# w076x.net
KiCad netlist of a schematic drawn in EAGLE
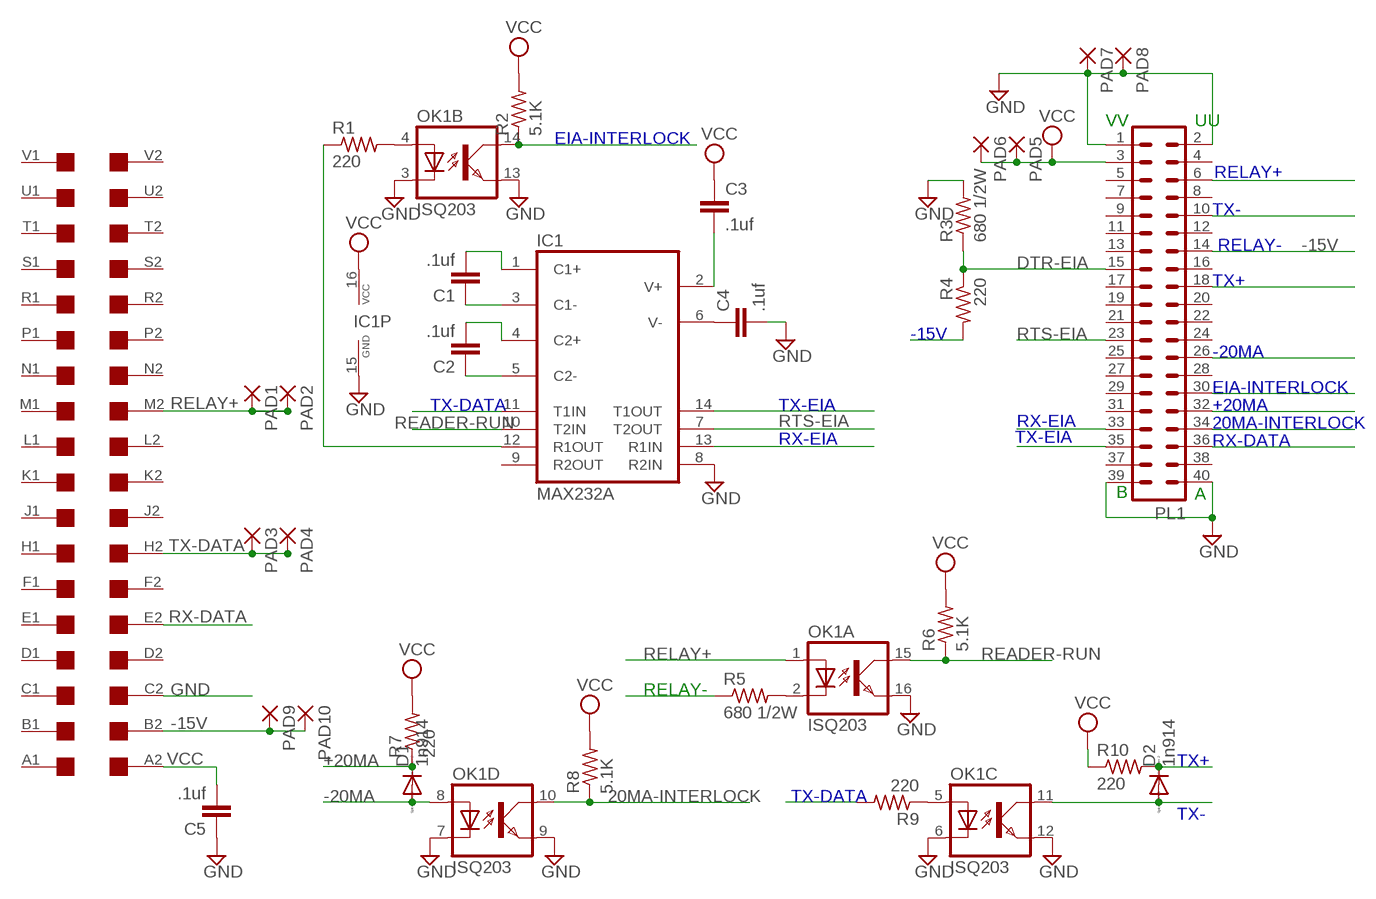
[diagram p0: schematic, sheet 1]

(export (version "E")
  (design (tool "Eeschema 10.0.6"))
  (components
    (comp (ref "C1")
      (value ".1uf")
      (footprint "eagle-import:C050-025X075")
      (libsource (lib "eagle-import") (part "C-EU050-025X075"))
    )
    (comp (ref "C2")
      (value ".1uf")
      (footprint "eagle-import:C050-025X075")
      (libsource (lib "eagle-import") (part "C-EU050-025X075"))
    )
    (comp (ref "C3")
      (value ".1uf")
      (footprint "eagle-import:C050-025X075")
      (libsource (lib "eagle-import") (part "C-EU050-025X075"))
    )
    (comp (ref "C4")
      (value ".1uf")
      (footprint "eagle-import:C050-025X075")
      (libsource (lib "eagle-import") (part "C-EU050-025X075"))
    )
    (comp (ref "C5")
      (value ".1uf")
      (footprint "eagle-import:C050-025X075")
      (libsource (lib "eagle-import") (part "C-EU050-025X075"))
    )
    (comp (ref "D1")
      (value "1n914")
      (footprint "eagle-import:DO41-10")
      (libsource (lib "eagle-import") (part "1N4004"))
    )
    (comp (ref "D2")
      (value "1n914")
      (footprint "eagle-import:DO41-10")
      (libsource (lib "eagle-import") (part "1N4004"))
    )
    (comp (ref "IC1")
      (value "MAX232A")
      (footprint "eagle-import:DIL16")
      (fields (field (name "MF") "MAXIM") (field (name "MPN") "MAX232ACPE+"))
      (libsource (lib "eagle-import") (part "MAX232"))
    )
    (comp (ref "OK1")
      (value "ISQ203")
      (footprint "eagle-import:DIL16")
      (fields (field (name "MF") "VISHAY/TELEFUNKEN") (field (name "MPN") "ILQ1"))
      (libsource (lib "eagle-import") (part "ILQ1"))
    )
    (comp (ref "PAD1")
      (value "1,6/0,8")
      (footprint "eagle-import:1,6_0,8")
      (libsource (lib "eagle-import") (part "1,6/0,8"))
    )
    (comp (ref "PAD2")
      (value "1,6/0,8")
      (footprint "eagle-import:1,6_0,8")
      (libsource (lib "eagle-import") (part "1,6/0,8"))
    )
    (comp (ref "PAD3")
      (value "1,6/0,8")
      (footprint "eagle-import:1,6_0,8")
      (libsource (lib "eagle-import") (part "1,6/0,8"))
    )
    (comp (ref "PAD4")
      (value "1,6/0,8")
      (footprint "eagle-import:1,6_0,8")
      (libsource (lib "eagle-import") (part "1,6/0,8"))
    )
    (comp (ref "PAD5")
      (value "1,6/0,8")
      (footprint "eagle-import:1,6_0,8")
      (libsource (lib "eagle-import") (part "1,6/0,8"))
    )
    (comp (ref "PAD6")
      (value "1,6/0,8")
      (footprint "eagle-import:1,6_0,8")
      (libsource (lib "eagle-import") (part "1,6/0,8"))
    )
    (comp (ref "PAD7")
      (value "1,6/0,8")
      (footprint "eagle-import:1,6_0,8")
      (libsource (lib "eagle-import") (part "1,6/0,8"))
    )
    (comp (ref "PAD8")
      (value "1,6/0,8")
      (footprint "eagle-import:1,6_0,8")
      (libsource (lib "eagle-import") (part "1,6/0,8"))
    )
    (comp (ref "PAD9")
      (value "1,6/0,8")
      (footprint "eagle-import:1,6_0,8")
      (libsource (lib "eagle-import") (part "1,6/0,8"))
    )
    (comp (ref "PAD10")
      (value "1,6/0,8")
      (footprint "eagle-import:1,6_0,8")
      (libsource (lib "eagle-import") (part "1,6/0,8"))
    )
    (comp (ref "PL1")
      (value "40H")
      (footprint "eagle-import:40H")
      (libsource (lib "eagle-import") (part "40H"))
    )
    (comp (ref "R1")
      (value "220")
      (footprint "eagle-import:0207_10")
      (libsource (lib "eagle-import") (part "R-US_0207/10"))
    )
    (comp (ref "R2")
      (value "5.1K")
      (footprint "eagle-import:0207_10")
      (libsource (lib "eagle-import") (part "R-US_0207/10"))
    )
    (comp (ref "R3")
      (value "680 1/2W")
      (footprint "eagle-import:0207_12")
      (libsource (lib "eagle-import") (part "R-US_0207/12"))
    )
    (comp (ref "R4")
      (value "220")
      (footprint "eagle-import:0207_10")
      (libsource (lib "eagle-import") (part "R-US_0207/10"))
    )
    (comp (ref "R5")
      (value "680 1/2W")
      (footprint "eagle-import:0207_12")
      (libsource (lib "eagle-import") (part "R-US_0207/12"))
    )
    (comp (ref "R6")
      (value "5.1K")
      (footprint "eagle-import:0207_10")
      (libsource (lib "eagle-import") (part "R-US_0207/10"))
    )
    (comp (ref "R7")
      (value "220")
      (footprint "eagle-import:0207_10")
      (libsource (lib "eagle-import") (part "R-US_0207/10"))
    )
    (comp (ref "R8")
      (value "5.1K")
      (footprint "eagle-import:0207_10")
      (libsource (lib "eagle-import") (part "R-US_0207/10"))
    )
    (comp (ref "R9")
      (value "220")
      (footprint "eagle-import:0207_10")
      (libsource (lib "eagle-import") (part "R-US_0207/10"))
    )
    (comp (ref "R10")
      (value "220")
      (footprint "eagle-import:0207_10")
      (libsource (lib "eagle-import") (part "R-US_0207/10"))
    )
    (comp (ref "U$1")
      (value "DEC-FLIPCHIP")
      (footprint "eagle-import:DEC-FLIPCHIP")
      (libsource (lib "eagle-import") (part "DEC-FLIPCHIP"))
    )
  )
  (nets
    (net (code "1") (name "/+20MA") (class "Default")
      (node (ref "D1") (pin "C") (pinfunction "C_C") (pintype "passive"))
      (node (ref "PL1") (pin "32") (pinfunction "32_32") (pintype "passive"))
      (node (ref "R7") (pin "1") (pinfunction "1_1") (pintype "passive"))
    )
    (net (code "2") (name "/-15V") (class "Default")
      (node (ref "PAD10") (pin "1") (pinfunction "P_1") (pintype "passive"))
      (node (ref "PAD9") (pin "1") (pinfunction "P_1") (pintype "passive"))
      (node (ref "PL1") (pin "14") (pinfunction "14_14") (pintype "passive"))
      (node (ref "R4") (pin "2") (pinfunction "2_2") (pintype "passive"))
      (node (ref "R5") (pin "1") (pinfunction "1_1") (pintype "passive"))
      (node (ref "U$1") (pin "B2") (pinfunction "B2_B2") (pintype "passive"))
    )
    (net (code "3") (name "/-20MA") (class "Default")
      (node (ref "D1") (pin "A") (pinfunction "A_A") (pintype "passive"))
      (node (ref "OK1") (pin "8") (pinfunction "A_8") (pintype "passive"))
      (node (ref "PL1") (pin "26") (pinfunction "26_26") (pintype "passive"))
    )
    (net (code "4") (name "/20MA-INTERLOCK") (class "Default")
      (node (ref "OK1") (pin "10") (pinfunction "COL_10") (pintype "passive"))
      (node (ref "PL1") (pin "34") (pinfunction "34_34") (pintype "passive"))
      (node (ref "R8") (pin "1") (pinfunction "1_1") (pintype "passive"))
    )
    (net (code "5") (name "/DTR-EIA") (class "Default")
      (node (ref "PL1") (pin "15") (pinfunction "15_15") (pintype "passive"))
      (node (ref "R3") (pin "1") (pinfunction "1_1") (pintype "passive"))
      (node (ref "R4") (pin "1") (pinfunction "1_1") (pintype "passive"))
    )
    (net (code "6") (name "/EIA-INTERLOCK") (class "Default")
      (node (ref "OK1") (pin "14") (pinfunction "COL_14") (pintype "passive"))
      (node (ref "PL1") (pin "30") (pinfunction "30_30") (pintype "passive"))
      (node (ref "R2") (pin "1") (pinfunction "1_1") (pintype "passive"))
    )
    (net (code "7") (name "/READER-RUN") (class "Default")
      (node (ref "IC1") (pin "10") (pinfunction "T2IN_10") (pintype "input"))
      (node (ref "OK1") (pin "15") (pinfunction "COL_15") (pintype "passive"))
      (node (ref "R6") (pin "1") (pinfunction "1_1") (pintype "passive"))
    )
    (net (code "8") (name "/RELAY+") (class "Default")
      (node (ref "OK1") (pin "1") (pinfunction "A_1") (pintype "passive"))
      (node (ref "PAD1") (pin "1") (pinfunction "P_1") (pintype "passive"))
      (node (ref "PAD2") (pin "1") (pinfunction "P_1") (pintype "passive"))
      (node (ref "PL1") (pin "6") (pinfunction "6_6") (pintype "passive"))
      (node (ref "U$1") (pin "M2") (pinfunction "M2_M2") (pintype "passive"))
    )
    (net (code "9") (name "/RTS-EIA") (class "Default")
      (node (ref "IC1") (pin "7") (pinfunction "T2OUT_7") (pintype "output"))
      (node (ref "PL1") (pin "23") (pinfunction "23_23") (pintype "passive"))
    )
    (net (code "10") (name "/RX-DATA") (class "Default")
      (node (ref "PL1") (pin "36") (pinfunction "36_36") (pintype "passive"))
      (node (ref "U$1") (pin "E2") (pinfunction "E2_E2") (pintype "passive"))
    )
    (net (code "11") (name "/RX-EIA") (class "Default")
      (node (ref "IC1") (pin "13") (pinfunction "R1IN_13") (pintype "input"))
      (node (ref "PL1") (pin "33") (pinfunction "33_33") (pintype "passive"))
    )
    (net (code "12") (name "/TX+") (class "Default")
      (node (ref "D2") (pin "C") (pinfunction "C_C") (pintype "passive"))
      (node (ref "PL1") (pin "18") (pinfunction "18_18") (pintype "passive"))
      (node (ref "R10") (pin "2") (pinfunction "2_2") (pintype "passive"))
    )
    (net (code "13") (name "/TX-") (class "Default")
      (node (ref "D2") (pin "A") (pinfunction "A_A") (pintype "passive"))
      (node (ref "OK1") (pin "11") (pinfunction "COL_11") (pintype "passive"))
      (node (ref "PL1") (pin "10") (pinfunction "10_10") (pintype "passive"))
    )
    (net (code "14") (name "/TX-DATA") (class "Default")
      (node (ref "IC1") (pin "11") (pinfunction "T1IN_11") (pintype "input"))
      (node (ref "PAD3") (pin "1") (pinfunction "P_1") (pintype "passive"))
      (node (ref "PAD4") (pin "1") (pinfunction "P_1") (pintype "passive"))
      (node (ref "R9") (pin "2") (pinfunction "2_2") (pintype "passive"))
      (node (ref "U$1") (pin "H2") (pinfunction "H2_H2") (pintype "passive"))
    )
    (net (code "15") (name "/TX-EIA") (class "Default")
      (node (ref "IC1") (pin "14") (pinfunction "T1OUT_14") (pintype "output"))
      (node (ref "PL1") (pin "35") (pinfunction "35_35") (pintype "passive"))
    )
    (net (code "16") (name "GND") (class "Default")
      (node (ref "C4") (pin "2") (pinfunction "2_2") (pintype "passive"))
      (node (ref "C5") (pin "1") (pinfunction "1_1") (pintype "passive"))
      (node (ref "IC1") (pin "15") (pinfunction "GND_15") (pintype "power_in"))
      (node (ref "IC1") (pin "8") (pinfunction "R2IN_8") (pintype "input"))
      (node (ref "OK1") (pin "12") (pinfunction "EMIT_12") (pintype "passive"))
      (node (ref "OK1") (pin "13") (pinfunction "EMIT_13") (pintype "passive"))
      (node (ref "OK1") (pin "16") (pinfunction "EMIT_16") (pintype "passive"))
      (node (ref "OK1") (pin "3") (pinfunction "C_3") (pintype "passive"))
      (node (ref "OK1") (pin "6") (pinfunction "C_6") (pintype "passive"))
      (node (ref "OK1") (pin "7") (pinfunction "C_7") (pintype "passive"))
      (node (ref "OK1") (pin "9") (pinfunction "EMIT_9") (pintype "passive"))
      (node (ref "PAD7") (pin "1") (pinfunction "P_1") (pintype "passive"))
      (node (ref "PAD8") (pin "1") (pinfunction "P_1") (pintype "passive"))
      (node (ref "PL1") (pin "1") (pinfunction "1_1") (pintype "passive"))
      (node (ref "PL1") (pin "2") (pinfunction "2_2") (pintype "passive"))
      (node (ref "PL1") (pin "39") (pinfunction "39_39") (pintype "passive"))
      (node (ref "PL1") (pin "40") (pinfunction "40_40") (pintype "passive"))
      (node (ref "R3") (pin "2") (pinfunction "2_2") (pintype "passive"))
      (node (ref "U$1") (pin "C2") (pinfunction "C2_C2") (pintype "passive"))
    )
    (net (code "17") (name "Net-(IC1A-C1+)") (class "Default")
      (node (ref "C1") (pin "2") (pinfunction "2_2") (pintype "passive"))
      (node (ref "IC1") (pin "1") (pinfunction "C1+_1") (pintype "bidirectional"))
    )
    (net (code "18") (name "Net-(IC1A-C1-)") (class "Default")
      (node (ref "C1") (pin "1") (pinfunction "1_1") (pintype "passive"))
      (node (ref "IC1") (pin "3") (pinfunction "C1-_3") (pintype "bidirectional"))
    )
    (net (code "19") (name "Net-(IC1A-C2+)") (class "Default")
      (node (ref "C2") (pin "2") (pinfunction "2_2") (pintype "passive"))
      (node (ref "IC1") (pin "4") (pinfunction "C2+_4") (pintype "bidirectional"))
    )
    (net (code "20") (name "Net-(IC1A-C2-)") (class "Default")
      (node (ref "C2") (pin "1") (pinfunction "1_1") (pintype "passive"))
      (node (ref "IC1") (pin "5") (pinfunction "C2-_5") (pintype "bidirectional"))
    )
    (net (code "21") (name "Net-(IC1A-R1OUT)") (class "Default")
      (node (ref "IC1") (pin "12") (pinfunction "R1OUT_12") (pintype "output"))
      (node (ref "R1") (pin "1") (pinfunction "1_1") (pintype "passive"))
    )
    (net (code "22") (name "Net-(IC1A-V+)") (class "Default")
      (node (ref "C3") (pin "2") (pinfunction "2_2") (pintype "passive"))
      (node (ref "IC1") (pin "2") (pinfunction "V+_2") (pintype "bidirectional"))
    )
    (net (code "23") (name "Net-(IC1A-V-)") (class "Default")
      (node (ref "C4") (pin "1") (pinfunction "1_1") (pintype "passive"))
      (node (ref "IC1") (pin "6") (pinfunction "V-_6") (pintype "bidirectional"))
    )
    (net (code "24") (name "Net-(OK1A-C)") (class "Default")
      (node (ref "OK1") (pin "2") (pinfunction "C_2") (pintype "passive"))
      (node (ref "R5") (pin "2") (pinfunction "2_2") (pintype "passive"))
    )
    (net (code "25") (name "Net-(OK1B-A)") (class "Default")
      (node (ref "OK1") (pin "4") (pinfunction "A_4") (pintype "passive"))
      (node (ref "R1") (pin "2") (pinfunction "2_2") (pintype "passive"))
    )
    (net (code "26") (name "Net-(OK1C-A)") (class "Default")
      (node (ref "OK1") (pin "5") (pinfunction "A_5") (pintype "passive"))
      (node (ref "R9") (pin "1") (pinfunction "1_1") (pintype "passive"))
    )
    (net (code "27") (name "VCC") (class "Default")
      (node (ref "C3") (pin "1") (pinfunction "1_1") (pintype "passive"))
      (node (ref "C5") (pin "2") (pinfunction "2_2") (pintype "passive"))
      (node (ref "IC1") (pin "16") (pinfunction "VCC_16") (pintype "power_in"))
      (node (ref "PAD5") (pin "1") (pinfunction "P_1") (pintype "passive"))
      (node (ref "PAD6") (pin "1") (pinfunction "P_1") (pintype "passive"))
      (node (ref "PL1") (pin "3") (pinfunction "3_3") (pintype "passive"))
      (node (ref "R10") (pin "1") (pinfunction "1_1") (pintype "passive"))
      (node (ref "R2") (pin "2") (pinfunction "2_2") (pintype "passive"))
      (node (ref "R6") (pin "2") (pinfunction "2_2") (pintype "passive"))
      (node (ref "R7") (pin "2") (pinfunction "2_2") (pintype "passive"))
      (node (ref "R8") (pin "2") (pinfunction "2_2") (pintype "passive"))
      (node (ref "U$1") (pin "A2") (pinfunction "A2_A2") (pintype "passive"))
    )
    (net (code "28") (name "unconnected-(IC1A-R2OUT-Pad9)") (class "Default")
      (node (ref "IC1") (pin "9") (pinfunction "R2OUT_9") (pintype "output"))
    )
    (net (code "29") (name "unconnected-(PL1-Pad4)") (class "Default")
      (node (ref "PL1") (pin "4") (pinfunction "4_4") (pintype "passive"))
    )
    (net (code "30") (name "unconnected-(PL1-Pad5)") (class "Default")
      (node (ref "PL1") (pin "5") (pinfunction "5_5") (pintype "passive"))
    )
    (net (code "31") (name "unconnected-(PL1-Pad7)") (class "Default")
      (node (ref "PL1") (pin "7") (pinfunction "7_7") (pintype "passive"))
    )
    (net (code "32") (name "unconnected-(PL1-Pad8)") (class "Default")
      (node (ref "PL1") (pin "8") (pinfunction "8_8") (pintype "passive"))
    )
    (net (code "33") (name "unconnected-(PL1-Pad9)") (class "Default")
      (node (ref "PL1") (pin "9") (pinfunction "9_9") (pintype "passive"))
    )
    (net (code "34") (name "unconnected-(PL1-Pad11)") (class "Default")
      (node (ref "PL1") (pin "11") (pinfunction "11_11") (pintype "passive"))
    )
    (net (code "35") (name "unconnected-(PL1-Pad12)") (class "Default")
      (node (ref "PL1") (pin "12") (pinfunction "12_12") (pintype "passive"))
    )
    (net (code "36") (name "unconnected-(PL1-Pad13)") (class "Default")
      (node (ref "PL1") (pin "13") (pinfunction "13_13") (pintype "passive"))
    )
    (net (code "37") (name "unconnected-(PL1-Pad16)") (class "Default")
      (node (ref "PL1") (pin "16") (pinfunction "16_16") (pintype "passive"))
    )
    (net (code "38") (name "unconnected-(PL1-Pad17)") (class "Default")
      (node (ref "PL1") (pin "17") (pinfunction "17_17") (pintype "passive"))
    )
    (net (code "39") (name "unconnected-(PL1-Pad19)") (class "Default")
      (node (ref "PL1") (pin "19") (pinfunction "19_19") (pintype "passive"))
    )
    (net (code "40") (name "unconnected-(PL1-Pad20)") (class "Default")
      (node (ref "PL1") (pin "20") (pinfunction "20_20") (pintype "passive"))
    )
    (net (code "41") (name "unconnected-(PL1-Pad21)") (class "Default")
      (node (ref "PL1") (pin "21") (pinfunction "21_21") (pintype "passive"))
    )
    (net (code "42") (name "unconnected-(PL1-Pad22)") (class "Default")
      (node (ref "PL1") (pin "22") (pinfunction "22_22") (pintype "passive"))
    )
    (net (code "43") (name "unconnected-(PL1-Pad24)") (class "Default")
      (node (ref "PL1") (pin "24") (pinfunction "24_24") (pintype "passive"))
    )
    (net (code "44") (name "unconnected-(PL1-Pad25)") (class "Default")
      (node (ref "PL1") (pin "25") (pinfunction "25_25") (pintype "passive"))
    )
    (net (code "45") (name "unconnected-(PL1-Pad27)") (class "Default")
      (node (ref "PL1") (pin "27") (pinfunction "27_27") (pintype "passive"))
    )
    (net (code "46") (name "unconnected-(PL1-Pad28)") (class "Default")
      (node (ref "PL1") (pin "28") (pinfunction "28_28") (pintype "passive"))
    )
    (net (code "47") (name "unconnected-(PL1-Pad29)") (class "Default")
      (node (ref "PL1") (pin "29") (pinfunction "29_29") (pintype "passive"))
    )
    (net (code "48") (name "unconnected-(PL1-Pad31)") (class "Default")
      (node (ref "PL1") (pin "31") (pinfunction "31_31") (pintype "passive"))
    )
    (net (code "49") (name "unconnected-(PL1-Pad37)") (class "Default")
      (node (ref "PL1") (pin "37") (pinfunction "37_37") (pintype "passive"))
    )
    (net (code "50") (name "unconnected-(PL1-Pad38)") (class "Default")
      (node (ref "PL1") (pin "38") (pinfunction "38_38") (pintype "passive"))
    )
    (net (code "51") (name "unconnected-(U$1-PadA1)") (class "Default")
      (node (ref "U$1") (pin "A1") (pinfunction "A1_A1") (pintype "passive"))
    )
    (net (code "52") (name "unconnected-(U$1-PadB1)") (class "Default")
      (node (ref "U$1") (pin "B1") (pinfunction "B1_B1") (pintype "passive"))
    )
    (net (code "53") (name "unconnected-(U$1-PadC1)") (class "Default")
      (node (ref "U$1") (pin "C1") (pinfunction "C1_C1") (pintype "passive"))
    )
    (net (code "54") (name "unconnected-(U$1-PadD1)") (class "Default")
      (node (ref "U$1") (pin "D1") (pinfunction "D1_D1") (pintype "passive"))
    )
    (net (code "55") (name "unconnected-(U$1-PadD2)") (class "Default")
      (node (ref "U$1") (pin "D2") (pinfunction "D2_D2") (pintype "passive"))
    )
    (net (code "56") (name "unconnected-(U$1-PadE1)") (class "Default")
      (node (ref "U$1") (pin "E1") (pinfunction "E1_E1") (pintype "passive"))
    )
    (net (code "57") (name "unconnected-(U$1-PadF1)") (class "Default")
      (node (ref "U$1") (pin "F1") (pinfunction "F1_F1") (pintype "passive"))
    )
    (net (code "58") (name "unconnected-(U$1-PadF2)") (class "Default")
      (node (ref "U$1") (pin "F2") (pinfunction "F2_F2") (pintype "passive"))
    )
    (net (code "59") (name "unconnected-(U$1-PadH1)") (class "Default")
      (node (ref "U$1") (pin "H1") (pinfunction "H1_H1") (pintype "passive"))
    )
    (net (code "60") (name "unconnected-(U$1-PadJ1)") (class "Default")
      (node (ref "U$1") (pin "J1") (pinfunction "J1_J1") (pintype "passive"))
    )
    (net (code "61") (name "unconnected-(U$1-PadJ2)") (class "Default")
      (node (ref "U$1") (pin "J2") (pinfunction "J2_J2") (pintype "passive"))
    )
    (net (code "62") (name "unconnected-(U$1-PadK1)") (class "Default")
      (node (ref "U$1") (pin "K1") (pinfunction "K1_K1") (pintype "passive"))
    )
    (net (code "63") (name "unconnected-(U$1-PadK2)") (class "Default")
      (node (ref "U$1") (pin "K2") (pinfunction "K2_K2") (pintype "passive"))
    )
    (net (code "64") (name "unconnected-(U$1-PadL1)") (class "Default")
      (node (ref "U$1") (pin "L1") (pinfunction "L1_L1") (pintype "passive"))
    )
    (net (code "65") (name "unconnected-(U$1-PadL2)") (class "Default")
      (node (ref "U$1") (pin "L2") (pinfunction "L2_L2") (pintype "passive"))
    )
    (net (code "66") (name "unconnected-(U$1-PadM1)") (class "Default")
      (node (ref "U$1") (pin "M1") (pinfunction "M1_M1") (pintype "passive"))
    )
    (net (code "67") (name "unconnected-(U$1-PadN1)") (class "Default")
      (node (ref "U$1") (pin "N1") (pinfunction "N1_N1") (pintype "passive"))
    )
    (net (code "68") (name "unconnected-(U$1-PadN2)") (class "Default")
      (node (ref "U$1") (pin "N2") (pinfunction "N2_N2") (pintype "passive"))
    )
    (net (code "69") (name "unconnected-(U$1-PadP1)") (class "Default")
      (node (ref "U$1") (pin "P1") (pinfunction "P1_P1") (pintype "passive"))
    )
    (net (code "70") (name "unconnected-(U$1-PadP2)") (class "Default")
      (node (ref "U$1") (pin "P2") (pinfunction "P2_P2") (pintype "passive"))
    )
    (net (code "71") (name "unconnected-(U$1-PadR1)") (class "Default")
      (node (ref "U$1") (pin "R1") (pinfunction "R1_R1") (pintype "passive"))
    )
    (net (code "72") (name "unconnected-(U$1-PadR2)") (class "Default")
      (node (ref "U$1") (pin "R2") (pinfunction "R2_R2") (pintype "passive"))
    )
    (net (code "73") (name "unconnected-(U$1-PadS1)") (class "Default")
      (node (ref "U$1") (pin "S1") (pinfunction "S1_S1") (pintype "passive"))
    )
    (net (code "74") (name "unconnected-(U$1-PadS2)") (class "Default")
      (node (ref "U$1") (pin "S2") (pinfunction "S2_S2") (pintype "passive"))
    )
    (net (code "75") (name "unconnected-(U$1-PadT1)") (class "Default")
      (node (ref "U$1") (pin "T1") (pinfunction "T1_T1") (pintype "passive"))
    )
    (net (code "76") (name "unconnected-(U$1-PadT2)") (class "Default")
      (node (ref "U$1") (pin "T2") (pinfunction "T2_T2") (pintype "passive"))
    )
    (net (code "77") (name "unconnected-(U$1-PadU1)") (class "Default")
      (node (ref "U$1") (pin "U1") (pinfunction "U1_U1") (pintype "passive"))
    )
    (net (code "78") (name "unconnected-(U$1-PadU2)") (class "Default")
      (node (ref "U$1") (pin "U2") (pinfunction "U2_U2") (pintype "passive"))
    )
    (net (code "79") (name "unconnected-(U$1-PadV1)") (class "Default")
      (node (ref "U$1") (pin "V1") (pinfunction "V1_V1") (pintype "passive"))
    )
    (net (code "80") (name "unconnected-(U$1-PadV2)") (class "Default")
      (node (ref "U$1") (pin "V2") (pinfunction "V2_V2") (pintype "passive"))
    )
  )
)
